# breakout.net
KiCad netlist of a schematic drawn in EAGLE
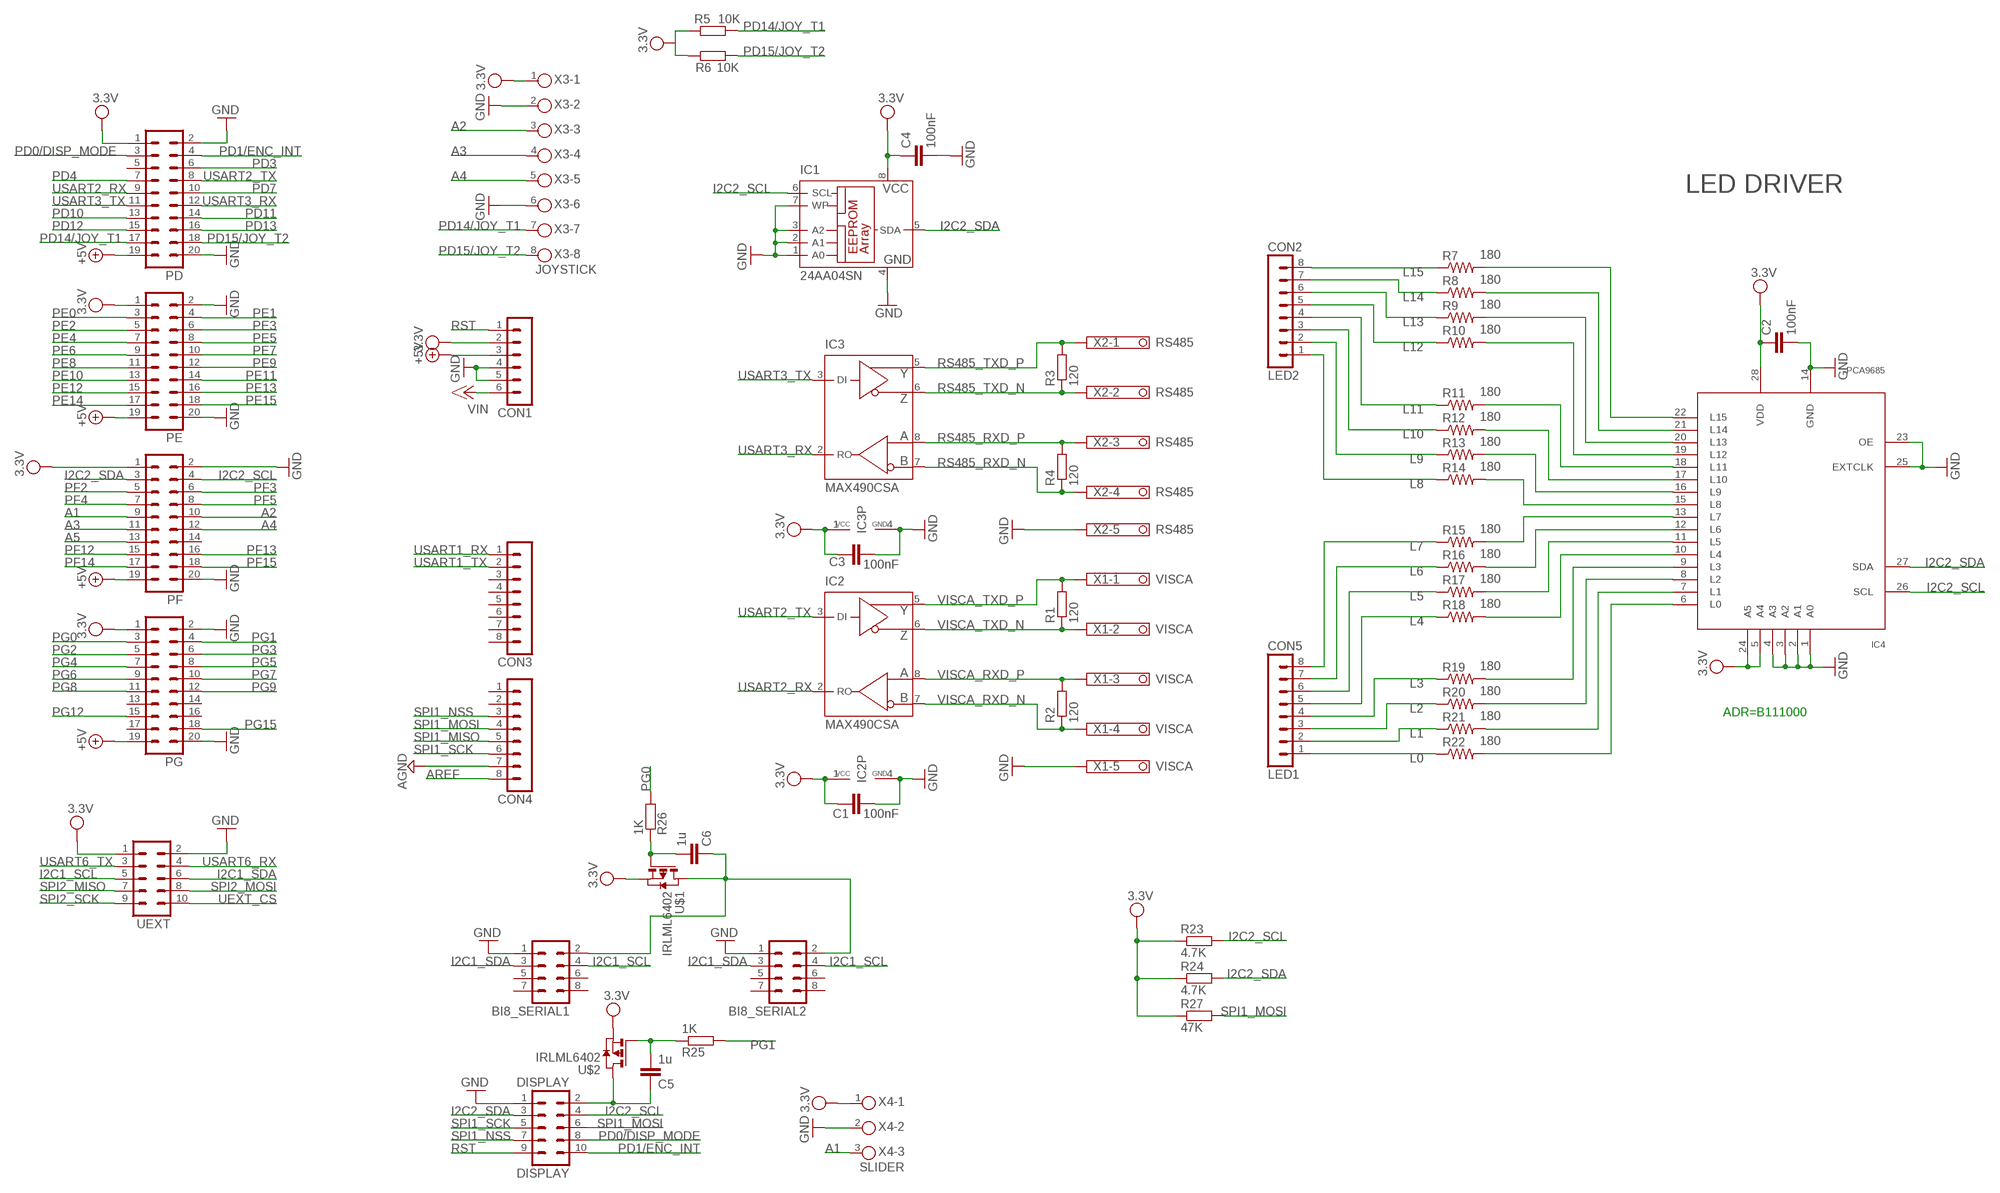
[diagram p0: schematic, sheet 1]

(export (version "E")
  (design (tool "Eeschema 10.0.6"))
  (components
    (comp (ref "BI8_SERIAL1")
      (value "MA04-2")
      (footprint "eagle-import:MA04-2")
      (libsource (lib "eagle-import") (part "MA04-2"))
    )
    (comp (ref "BI8_SERIAL2")
      (value "MA04-2")
      (footprint "eagle-import:MA04-2")
      (libsource (lib "eagle-import") (part "MA04-2"))
    )
    (comp (ref "C1")
      (value "100nF")
      (footprint "eagle-import:0603-CAP")
      (libsource (lib "eagle-import") (part "CAP0603-CAP"))
    )
    (comp (ref "C2")
      (value "100nF")
      (footprint "eagle-import:0603-CAP")
      (libsource (lib "eagle-import") (part "CAP0603-CAP"))
    )
    (comp (ref "C3")
      (value "100nF")
      (footprint "eagle-import:0603-CAP")
      (libsource (lib "eagle-import") (part "CAP0603-CAP"))
    )
    (comp (ref "C4")
      (value "100nF")
      (footprint "eagle-import:0603-CAP")
      (libsource (lib "eagle-import") (part "CAP0603-CAP"))
    )
    (comp (ref "C5")
      (value "1u")
      (footprint "eagle-import:C0805")
      (libsource (lib "eagle-import") (part "C-EUC0805"))
    )
    (comp (ref "C6")
      (value "1u")
      (footprint "eagle-import:C0805")
      (libsource (lib "eagle-import") (part "C-EUC0805"))
    )
    (comp (ref "CON1")
      (value "MA06-1")
      (footprint "eagle-import:MA06-1")
      (libsource (lib "eagle-import") (part "MA06-1"))
    )
    (comp (ref "CON2")
      (value "LED2")
      (footprint "eagle-import:MA08-1")
      (libsource (lib "eagle-import") (part "MA08-1"))
    )
    (comp (ref "CON3")
      (value "MA08-1")
      (footprint "eagle-import:MA08-1")
      (libsource (lib "eagle-import") (part "MA08-1"))
    )
    (comp (ref "CON4")
      (value "MA08-1")
      (footprint "eagle-import:MA08-1")
      (libsource (lib "eagle-import") (part "MA08-1"))
    )
    (comp (ref "CON5")
      (value "LED1")
      (footprint "eagle-import:MA08-1")
      (libsource (lib "eagle-import") (part "MA08-1"))
    )
    (comp (ref "DISPLAY")
      (value "DISPLAY")
      (footprint "eagle-import:MA05-2")
      (libsource (lib "eagle-import") (part "MA05-2"))
    )
    (comp (ref "IC1")
      (value "24AA04SN")
      (footprint "eagle-import:SO-08")
      (fields (field (name "MF") "MICROCHIP") (field (name "MPN") "24AA04/SN"))
      (libsource (lib "eagle-import") (part "24SNAA04"))
    )
    (comp (ref "IC2")
      (value "MAX490CSA")
      (footprint "eagle-import:SO08")
      (fields (field (name "MF") "MAXIM") (field (name "MPN") "MAX488CSA"))
      (libsource (lib "eagle-import") (part "MAX488CSA"))
    )
    (comp (ref "IC3")
      (value "MAX490CSA")
      (footprint "eagle-import:SO08")
      (fields (field (name "MF") "MAXIM") (field (name "MPN") "MAX488CSA"))
      (libsource (lib "eagle-import") (part "MAX488CSA"))
    )
    (comp (ref "IC4")
      (value "PCA9685")
      (footprint "eagle-import:TSSOP28")
      (libsource (lib "eagle-import") (part "PCA9685"))
    )
    (comp (ref "PD")
      (value "MA10-2")
      (footprint "eagle-import:MA10-2")
      (libsource (lib "eagle-import") (part "MA10-2"))
    )
    (comp (ref "PE")
      (value "MA10-2")
      (footprint "eagle-import:MA10-2")
      (libsource (lib "eagle-import") (part "MA10-2"))
    )
    (comp (ref "PF")
      (value "MA10-2")
      (footprint "eagle-import:MA10-2")
      (libsource (lib "eagle-import") (part "MA10-2"))
    )
    (comp (ref "PG")
      (value "MA10-2")
      (footprint "eagle-import:MA10-2")
      (libsource (lib "eagle-import") (part "MA10-2"))
    )
    (comp (ref "R1")
      (value "120")
      (footprint "eagle-import:R0603")
      (libsource (lib "eagle-import") (part "R-EU_R0603"))
    )
    (comp (ref "R2")
      (value "120")
      (footprint "eagle-import:R0603")
      (libsource (lib "eagle-import") (part "R-EU_R0603"))
    )
    (comp (ref "R3")
      (value "120")
      (footprint "eagle-import:R0603")
      (libsource (lib "eagle-import") (part "R-EU_R0603"))
    )
    (comp (ref "R4")
      (value "120")
      (footprint "eagle-import:R0603")
      (libsource (lib "eagle-import") (part "R-EU_R0603"))
    )
    (comp (ref "R5")
      (value "10K")
      (footprint "eagle-import:R0603")
      (libsource (lib "eagle-import") (part "R-EU_R0603"))
    )
    (comp (ref "R6")
      (value "10K")
      (footprint "eagle-import:R0603")
      (libsource (lib "eagle-import") (part "R-EU_R0603"))
    )
    (comp (ref "R7")
      (value "180")
      (footprint "eagle-import:0603-RES")
      (libsource (lib "eagle-import") (part "RESISTOR0603-RES"))
    )
    (comp (ref "R8")
      (value "180")
      (footprint "eagle-import:0603-RES")
      (libsource (lib "eagle-import") (part "RESISTOR0603-RES"))
    )
    (comp (ref "R9")
      (value "180")
      (footprint "eagle-import:0603-RES")
      (libsource (lib "eagle-import") (part "RESISTOR0603-RES"))
    )
    (comp (ref "R10")
      (value "180")
      (footprint "eagle-import:0603-RES")
      (libsource (lib "eagle-import") (part "RESISTOR0603-RES"))
    )
    (comp (ref "R11")
      (value "180")
      (footprint "eagle-import:0603-RES")
      (libsource (lib "eagle-import") (part "RESISTOR0603-RES"))
    )
    (comp (ref "R12")
      (value "180")
      (footprint "eagle-import:0603-RES")
      (libsource (lib "eagle-import") (part "RESISTOR0603-RES"))
    )
    (comp (ref "R13")
      (value "180")
      (footprint "eagle-import:0603-RES")
      (libsource (lib "eagle-import") (part "RESISTOR0603-RES"))
    )
    (comp (ref "R14")
      (value "180")
      (footprint "eagle-import:0603-RES")
      (libsource (lib "eagle-import") (part "RESISTOR0603-RES"))
    )
    (comp (ref "R15")
      (value "180")
      (footprint "eagle-import:0603-RES")
      (libsource (lib "eagle-import") (part "RESISTOR0603-RES"))
    )
    (comp (ref "R16")
      (value "180")
      (footprint "eagle-import:0603-RES")
      (libsource (lib "eagle-import") (part "RESISTOR0603-RES"))
    )
    (comp (ref "R17")
      (value "180")
      (footprint "eagle-import:0603-RES")
      (libsource (lib "eagle-import") (part "RESISTOR0603-RES"))
    )
    (comp (ref "R18")
      (value "180")
      (footprint "eagle-import:0603-RES")
      (libsource (lib "eagle-import") (part "RESISTOR0603-RES"))
    )
    (comp (ref "R19")
      (value "180")
      (footprint "eagle-import:0603-RES")
      (libsource (lib "eagle-import") (part "RESISTOR0603-RES"))
    )
    (comp (ref "R20")
      (value "180")
      (footprint "eagle-import:0603-RES")
      (libsource (lib "eagle-import") (part "RESISTOR0603-RES"))
    )
    (comp (ref "R21")
      (value "180")
      (footprint "eagle-import:0603-RES")
      (libsource (lib "eagle-import") (part "RESISTOR0603-RES"))
    )
    (comp (ref "R22")
      (value "180")
      (footprint "eagle-import:0603-RES")
      (libsource (lib "eagle-import") (part "RESISTOR0603-RES"))
    )
    (comp (ref "R23")
      (value "4.7K")
      (footprint "eagle-import:R0603")
      (libsource (lib "eagle-import") (part "R-EU_R0603"))
    )
    (comp (ref "R24")
      (value "4.7K")
      (footprint "eagle-import:R0603")
      (libsource (lib "eagle-import") (part "R-EU_R0603"))
    )
    (comp (ref "R25")
      (value "1K")
      (footprint "eagle-import:R0603")
      (libsource (lib "eagle-import") (part "R-EU_R0603"))
    )
    (comp (ref "R26")
      (value "1K")
      (footprint "eagle-import:R0603")
      (libsource (lib "eagle-import") (part "R-EU_R0603"))
    )
    (comp (ref "R27")
      (value "47K")
      (footprint "eagle-import:R0603")
      (libsource (lib "eagle-import") (part "R-EU_R0603"))
    )
    (comp (ref "U$1")
      (value "IRLML6402")
      (footprint "eagle-import:SOT-23")
      (libsource (lib "eagle-import") (part "IRLML6402"))
    )
    (comp (ref "U$2")
      (value "IRLML6402")
      (footprint "eagle-import:SOT-23")
      (libsource (lib "eagle-import") (part "IRLML6402"))
    )
    (comp (ref "UEXT")
      (value "ML10L")
      (footprint "eagle-import:ML10L")
      (libsource (lib "eagle-import") (part "ML10L"))
    )
    (comp (ref "X1")
      (value "VISCA")
      (footprint "eagle-import:1751277")
      (libsource (lib "eagle-import") (part "1751277"))
    )
    (comp (ref "X2")
      (value "RS485")
      (footprint "eagle-import:1751277")
      (libsource (lib "eagle-import") (part "1751277"))
    )
    (comp (ref "X3")
      (value "JOYSTICK")
      (footprint "eagle-import:8POL35")
      (libsource (lib "eagle-import") (part "AKL59-08"))
    )
    (comp (ref "X4")
      (value "SLIDER")
      (footprint "eagle-import:3POL35")
      (libsource (lib "eagle-import") (part "AKL59-03"))
    )
  )
  (nets
    (net (code "1") (name "+5V") (class "Default")
      (node (ref "CON1") (pin "3") (pinfunction "3_3") (pintype "passive"))
      (node (ref "PD") (pin "19") (pinfunction "19_19") (pintype "passive"))
      (node (ref "PE") (pin "19") (pinfunction "19_19") (pintype "passive"))
      (node (ref "PF") (pin "19") (pinfunction "19_19") (pintype "passive"))
      (node (ref "PG") (pin "19") (pinfunction "19_19") (pintype "passive"))
    )
    (net (code "2") (name "/A1") (class "Default")
      (node (ref "PF") (pin "9") (pinfunction "9_9") (pintype "passive"))
      (node (ref "X4") (pin "3") (pinfunction "1_3") (pintype "passive"))
    )
    (net (code "3") (name "/A2") (class "Default")
      (node (ref "PF") (pin "10") (pinfunction "10_10") (pintype "passive"))
      (node (ref "X3") (pin "3") (pinfunction "1_3") (pintype "passive"))
    )
    (net (code "4") (name "/A3") (class "Default")
      (node (ref "PF") (pin "11") (pinfunction "11_11") (pintype "passive"))
      (node (ref "X3") (pin "4") (pinfunction "1_4") (pintype "passive"))
    )
    (net (code "5") (name "/A4") (class "Default")
      (node (ref "PF") (pin "12") (pinfunction "12_12") (pintype "passive"))
      (node (ref "X3") (pin "5") (pinfunction "1_5") (pintype "passive"))
    )
    (net (code "6") (name "/A5") (class "Default")
      (node (ref "PF") (pin "13") (pinfunction "13_13") (pintype "passive"))
    )
    (net (code "7") (name "/AREF") (class "Default")
      (node (ref "CON4") (pin "8") (pinfunction "8_8") (pintype "passive"))
    )
    (net (code "8") (name "/I2C1_SCL") (class "Default")
      (node (ref "BI8_SERIAL1") (pin "4") (pinfunction "4_4") (pintype "passive"))
      (node (ref "BI8_SERIAL2") (pin "4") (pinfunction "4_4") (pintype "passive"))
      (node (ref "UEXT") (pin "5") (pinfunction "5_5") (pintype "passive"))
    )
    (net (code "9") (name "/I2C1_SDA") (class "Default")
      (node (ref "BI8_SERIAL1") (pin "3") (pinfunction "3_3") (pintype "passive"))
      (node (ref "BI8_SERIAL2") (pin "3") (pinfunction "3_3") (pintype "passive"))
      (node (ref "UEXT") (pin "6") (pinfunction "6_6") (pintype "passive"))
    )
    (net (code "10") (name "/I2C2_SCL") (class "Default")
      (node (ref "DISPLAY") (pin "4") (pinfunction "4_4") (pintype "passive"))
      (node (ref "IC1") (pin "6") (pinfunction "SCL_6") (pintype "input"))
      (node (ref "IC4") (pin "26") (pinfunction "SCL_26") (pintype "input"))
      (node (ref "PF") (pin "4") (pinfunction "4_4") (pintype "passive"))
      (node (ref "R23") (pin "2") (pinfunction "2_2") (pintype "passive"))
    )
    (net (code "11") (name "/I2C2_SDA") (class "Default")
      (node (ref "DISPLAY") (pin "3") (pinfunction "3_3") (pintype "passive"))
      (node (ref "IC1") (pin "5") (pinfunction "SDA_5") (pintype "bidirectional"))
      (node (ref "IC4") (pin "27") (pinfunction "SDA_27") (pintype "input"))
      (node (ref "PF") (pin "3") (pinfunction "3_3") (pintype "passive"))
      (node (ref "R24") (pin "2") (pinfunction "2_2") (pintype "passive"))
    )
    (net (code "12") (name "/L0") (class "Default")
      (node (ref "CON5") (pin "1") (pinfunction "1_1") (pintype "passive"))
      (node (ref "R22") (pin "1") (pinfunction "1_1") (pintype "passive"))
    )
    (net (code "13") (name "/L1") (class "Default")
      (node (ref "CON5") (pin "2") (pinfunction "2_2") (pintype "passive"))
      (node (ref "R21") (pin "1") (pinfunction "1_1") (pintype "passive"))
    )
    (net (code "14") (name "/L2") (class "Default")
      (node (ref "CON5") (pin "3") (pinfunction "3_3") (pintype "passive"))
      (node (ref "R20") (pin "1") (pinfunction "1_1") (pintype "passive"))
    )
    (net (code "15") (name "/L3") (class "Default")
      (node (ref "CON5") (pin "4") (pinfunction "4_4") (pintype "passive"))
      (node (ref "R19") (pin "1") (pinfunction "1_1") (pintype "passive"))
    )
    (net (code "16") (name "/L4") (class "Default")
      (node (ref "CON5") (pin "5") (pinfunction "5_5") (pintype "passive"))
      (node (ref "R18") (pin "1") (pinfunction "1_1") (pintype "passive"))
    )
    (net (code "17") (name "/L5") (class "Default")
      (node (ref "CON5") (pin "6") (pinfunction "6_6") (pintype "passive"))
      (node (ref "R17") (pin "1") (pinfunction "1_1") (pintype "passive"))
    )
    (net (code "18") (name "/L6") (class "Default")
      (node (ref "CON5") (pin "7") (pinfunction "7_7") (pintype "passive"))
      (node (ref "R16") (pin "1") (pinfunction "1_1") (pintype "passive"))
    )
    (net (code "19") (name "/L7") (class "Default")
      (node (ref "CON5") (pin "8") (pinfunction "8_8") (pintype "passive"))
      (node (ref "R15") (pin "1") (pinfunction "1_1") (pintype "passive"))
    )
    (net (code "20") (name "/L8") (class "Default")
      (node (ref "CON2") (pin "1") (pinfunction "1_1") (pintype "passive"))
      (node (ref "R14") (pin "1") (pinfunction "1_1") (pintype "passive"))
    )
    (net (code "21") (name "/L9") (class "Default")
      (node (ref "CON2") (pin "2") (pinfunction "2_2") (pintype "passive"))
      (node (ref "R13") (pin "1") (pinfunction "1_1") (pintype "passive"))
    )
    (net (code "22") (name "/L10") (class "Default")
      (node (ref "CON2") (pin "3") (pinfunction "3_3") (pintype "passive"))
      (node (ref "R12") (pin "1") (pinfunction "1_1") (pintype "passive"))
    )
    (net (code "23") (name "/L11") (class "Default")
      (node (ref "CON2") (pin "4") (pinfunction "4_4") (pintype "passive"))
      (node (ref "R11") (pin "1") (pinfunction "1_1") (pintype "passive"))
    )
    (net (code "24") (name "/L12") (class "Default")
      (node (ref "CON2") (pin "5") (pinfunction "5_5") (pintype "passive"))
      (node (ref "R10") (pin "1") (pinfunction "1_1") (pintype "passive"))
    )
    (net (code "25") (name "/L13") (class "Default")
      (node (ref "CON2") (pin "6") (pinfunction "6_6") (pintype "passive"))
      (node (ref "R9") (pin "1") (pinfunction "1_1") (pintype "passive"))
    )
    (net (code "26") (name "/L14") (class "Default")
      (node (ref "CON2") (pin "7") (pinfunction "7_7") (pintype "passive"))
      (node (ref "R8") (pin "1") (pinfunction "1_1") (pintype "passive"))
    )
    (net (code "27") (name "/L15") (class "Default")
      (node (ref "CON2") (pin "8") (pinfunction "8_8") (pintype "passive"))
      (node (ref "R7") (pin "1") (pinfunction "1_1") (pintype "passive"))
    )
    (net (code "28") (name "/PD0{slash}DISP_MODE") (class "Default")
      (node (ref "DISPLAY") (pin "8") (pinfunction "8_8") (pintype "passive"))
      (node (ref "PD") (pin "3") (pinfunction "3_3") (pintype "passive"))
    )
    (net (code "29") (name "/PD1{slash}ENC_INT") (class "Default")
      (node (ref "DISPLAY") (pin "10") (pinfunction "10_10") (pintype "passive"))
      (node (ref "PD") (pin "4") (pinfunction "4_4") (pintype "passive"))
    )
    (net (code "30") (name "/PD3") (class "Default")
      (node (ref "PD") (pin "6") (pinfunction "6_6") (pintype "passive"))
    )
    (net (code "31") (name "/PD4") (class "Default")
      (node (ref "PD") (pin "7") (pinfunction "7_7") (pintype "passive"))
    )
    (net (code "32") (name "/PD7") (class "Default")
      (node (ref "PD") (pin "10") (pinfunction "10_10") (pintype "passive"))
    )
    (net (code "33") (name "/PD10") (class "Default")
      (node (ref "PD") (pin "13") (pinfunction "13_13") (pintype "passive"))
    )
    (net (code "34") (name "/PD11") (class "Default")
      (node (ref "PD") (pin "14") (pinfunction "14_14") (pintype "passive"))
    )
    (net (code "35") (name "/PD12") (class "Default")
      (node (ref "PD") (pin "15") (pinfunction "15_15") (pintype "passive"))
    )
    (net (code "36") (name "/PD13") (class "Default")
      (node (ref "PD") (pin "16") (pinfunction "16_16") (pintype "passive"))
    )
    (net (code "37") (name "/PD14{slash}JOY_T1") (class "Default")
      (node (ref "PD") (pin "17") (pinfunction "17_17") (pintype "passive"))
      (node (ref "R5") (pin "2") (pinfunction "2_2") (pintype "passive"))
      (node (ref "X3") (pin "7") (pinfunction "1_7") (pintype "passive"))
    )
    (net (code "38") (name "/PD15{slash}JOY_T2") (class "Default")
      (node (ref "PD") (pin "18") (pinfunction "18_18") (pintype "passive"))
      (node (ref "R6") (pin "2") (pinfunction "2_2") (pintype "passive"))
      (node (ref "X3") (pin "8") (pinfunction "1_8") (pintype "passive"))
    )
    (net (code "39") (name "/PE0") (class "Default")
      (node (ref "PE") (pin "3") (pinfunction "3_3") (pintype "passive"))
    )
    (net (code "40") (name "/PE1") (class "Default")
      (node (ref "PE") (pin "4") (pinfunction "4_4") (pintype "passive"))
    )
    (net (code "41") (name "/PE2") (class "Default")
      (node (ref "PE") (pin "5") (pinfunction "5_5") (pintype "passive"))
    )
    (net (code "42") (name "/PE3") (class "Default")
      (node (ref "PE") (pin "6") (pinfunction "6_6") (pintype "passive"))
    )
    (net (code "43") (name "/PE4") (class "Default")
      (node (ref "PE") (pin "7") (pinfunction "7_7") (pintype "passive"))
    )
    (net (code "44") (name "/PE5") (class "Default")
      (node (ref "PE") (pin "8") (pinfunction "8_8") (pintype "passive"))
    )
    (net (code "45") (name "/PE6") (class "Default")
      (node (ref "PE") (pin "9") (pinfunction "9_9") (pintype "passive"))
    )
    (net (code "46") (name "/PE7") (class "Default")
      (node (ref "PE") (pin "10") (pinfunction "10_10") (pintype "passive"))
    )
    (net (code "47") (name "/PE8") (class "Default")
      (node (ref "PE") (pin "11") (pinfunction "11_11") (pintype "passive"))
    )
    (net (code "48") (name "/PE9") (class "Default")
      (node (ref "PE") (pin "12") (pinfunction "12_12") (pintype "passive"))
    )
    (net (code "49") (name "/PE10") (class "Default")
      (node (ref "PE") (pin "13") (pinfunction "13_13") (pintype "passive"))
    )
    (net (code "50") (name "/PE11") (class "Default")
      (node (ref "PE") (pin "14") (pinfunction "14_14") (pintype "passive"))
    )
    (net (code "51") (name "/PE12") (class "Default")
      (node (ref "PE") (pin "15") (pinfunction "15_15") (pintype "passive"))
    )
    (net (code "52") (name "/PE13") (class "Default")
      (node (ref "PE") (pin "16") (pinfunction "16_16") (pintype "passive"))
    )
    (net (code "53") (name "/PE14") (class "Default")
      (node (ref "PE") (pin "17") (pinfunction "17_17") (pintype "passive"))
    )
    (net (code "54") (name "/PE15") (class "Default")
      (node (ref "PE") (pin "18") (pinfunction "18_18") (pintype "passive"))
    )
    (net (code "55") (name "/PF2") (class "Default")
      (node (ref "PF") (pin "5") (pinfunction "5_5") (pintype "passive"))
    )
    (net (code "56") (name "/PF3") (class "Default")
      (node (ref "PF") (pin "6") (pinfunction "6_6") (pintype "passive"))
    )
    (net (code "57") (name "/PF4") (class "Default")
      (node (ref "PF") (pin "7") (pinfunction "7_7") (pintype "passive"))
    )
    (net (code "58") (name "/PF5") (class "Default")
      (node (ref "PF") (pin "8") (pinfunction "8_8") (pintype "passive"))
    )
    (net (code "59") (name "/PF12") (class "Default")
      (node (ref "PF") (pin "15") (pinfunction "15_15") (pintype "passive"))
    )
    (net (code "60") (name "/PF13") (class "Default")
      (node (ref "PF") (pin "16") (pinfunction "16_16") (pintype "passive"))
    )
    (net (code "61") (name "/PF14") (class "Default")
      (node (ref "PF") (pin "17") (pinfunction "17_17") (pintype "passive"))
    )
    (net (code "62") (name "/PF15") (class "Default")
      (node (ref "PF") (pin "18") (pinfunction "18_18") (pintype "passive"))
    )
    (net (code "63") (name "/PG0") (class "Default")
      (node (ref "PG") (pin "3") (pinfunction "3_3") (pintype "passive"))
      (node (ref "R26") (pin "2") (pinfunction "2_2") (pintype "passive"))
    )
    (net (code "64") (name "/PG1") (class "Default")
      (node (ref "PG") (pin "4") (pinfunction "4_4") (pintype "passive"))
      (node (ref "R25") (pin "2") (pinfunction "2_2") (pintype "passive"))
    )
    (net (code "65") (name "/PG2") (class "Default")
      (node (ref "PG") (pin "5") (pinfunction "5_5") (pintype "passive"))
    )
    (net (code "66") (name "/PG3") (class "Default")
      (node (ref "PG") (pin "6") (pinfunction "6_6") (pintype "passive"))
    )
    (net (code "67") (name "/PG4") (class "Default")
      (node (ref "PG") (pin "7") (pinfunction "7_7") (pintype "passive"))
    )
    (net (code "68") (name "/PG5") (class "Default")
      (node (ref "PG") (pin "8") (pinfunction "8_8") (pintype "passive"))
    )
    (net (code "69") (name "/PG6") (class "Default")
      (node (ref "PG") (pin "9") (pinfunction "9_9") (pintype "passive"))
    )
    (net (code "70") (name "/PG7") (class "Default")
      (node (ref "PG") (pin "10") (pinfunction "10_10") (pintype "passive"))
    )
    (net (code "71") (name "/PG8") (class "Default")
      (node (ref "PG") (pin "11") (pinfunction "11_11") (pintype "passive"))
    )
    (net (code "72") (name "/PG9") (class "Default")
      (node (ref "PG") (pin "12") (pinfunction "12_12") (pintype "passive"))
    )
    (net (code "73") (name "/PG12") (class "Default")
      (node (ref "PG") (pin "15") (pinfunction "15_15") (pintype "passive"))
    )
    (net (code "74") (name "/PG15") (class "Default")
      (node (ref "PG") (pin "18") (pinfunction "18_18") (pintype "passive"))
    )
    (net (code "75") (name "/RS485_RXD_N") (class "Default")
      (node (ref "IC3") (pin "7") (pinfunction "B_7") (pintype "input"))
      (node (ref "R4") (pin "1") (pinfunction "1_1") (pintype "passive"))
      (node (ref "X2") (pin "4") (pinfunction "K_4") (pintype "passive"))
    )
    (net (code "76") (name "/RS485_RXD_P") (class "Default")
      (node (ref "IC3") (pin "8") (pinfunction "A_8") (pintype "input"))
      (node (ref "R4") (pin "2") (pinfunction "2_2") (pintype "passive"))
      (node (ref "X2") (pin "3") (pinfunction "K_3") (pintype "passive"))
    )
    (net (code "77") (name "/RS485_TXD_N") (class "Default")
      (node (ref "IC3") (pin "6") (pinfunction "Z_6") (pintype "output"))
      (node (ref "R3") (pin "1") (pinfunction "1_1") (pintype "passive"))
      (node (ref "X2") (pin "2") (pinfunction "K_2") (pintype "passive"))
    )
    (net (code "78") (name "/RS485_TXD_P") (class "Default")
      (node (ref "IC3") (pin "5") (pinfunction "Y_5") (pintype "output"))
      (node (ref "R3") (pin "2") (pinfunction "2_2") (pintype "passive"))
      (node (ref "X2") (pin "1") (pinfunction "K_1") (pintype "passive"))
    )
    (net (code "79") (name "/RST") (class "Default")
      (node (ref "CON1") (pin "1") (pinfunction "1_1") (pintype "passive"))
      (node (ref "DISPLAY") (pin "9") (pinfunction "9_9") (pintype "passive"))
    )
    (net (code "80") (name "/SPI1_MISO") (class "Default")
      (node (ref "CON4") (pin "5") (pinfunction "5_5") (pintype "passive"))
    )
    (net (code "81") (name "/SPI1_MOSI") (class "Default")
      (node (ref "CON4") (pin "4") (pinfunction "4_4") (pintype "passive"))
      (node (ref "DISPLAY") (pin "6") (pinfunction "6_6") (pintype "passive"))
      (node (ref "R27") (pin "2") (pinfunction "2_2") (pintype "passive"))
    )
    (net (code "82") (name "/SPI1_NSS") (class "Default")
      (node (ref "CON4") (pin "3") (pinfunction "3_3") (pintype "passive"))
      (node (ref "DISPLAY") (pin "7") (pinfunction "7_7") (pintype "passive"))
    )
    (net (code "83") (name "/SPI1_SCK") (class "Default")
      (node (ref "CON4") (pin "6") (pinfunction "6_6") (pintype "passive"))
      (node (ref "DISPLAY") (pin "5") (pinfunction "5_5") (pintype "passive"))
    )
    (net (code "84") (name "/SPI2_MISO") (class "Default")
      (node (ref "UEXT") (pin "7") (pinfunction "7_7") (pintype "passive"))
    )
    (net (code "85") (name "/SPI2_MOSI") (class "Default")
      (node (ref "UEXT") (pin "8") (pinfunction "8_8") (pintype "passive"))
    )
    (net (code "86") (name "/SPI2_SCK") (class "Default")
      (node (ref "UEXT") (pin "9") (pinfunction "9_9") (pintype "passive"))
    )
    (net (code "87") (name "/UEXT_CS") (class "Default")
      (node (ref "UEXT") (pin "10") (pinfunction "10_10") (pintype "passive"))
    )
    (net (code "88") (name "/USART1_RX") (class "Default")
      (node (ref "CON3") (pin "1") (pinfunction "1_1") (pintype "passive"))
    )
    (net (code "89") (name "/USART1_TX") (class "Default")
      (node (ref "CON3") (pin "2") (pinfunction "2_2") (pintype "passive"))
    )
    (net (code "90") (name "/USART2_RX") (class "Default")
      (node (ref "IC2") (pin "2") (pinfunction "RO_2") (pintype "output"))
      (node (ref "PD") (pin "9") (pinfunction "9_9") (pintype "passive"))
    )
    (net (code "91") (name "/USART2_TX") (class "Default")
      (node (ref "IC2") (pin "3") (pinfunction "DI_3") (pintype "input"))
      (node (ref "PD") (pin "8") (pinfunction "8_8") (pintype "passive"))
    )
    (net (code "92") (name "/USART3_RX") (class "Default")
      (node (ref "IC3") (pin "2") (pinfunction "RO_2") (pintype "output"))
      (node (ref "PD") (pin "12") (pinfunction "12_12") (pintype "passive"))
    )
    (net (code "93") (name "/USART3_TX") (class "Default")
      (node (ref "IC3") (pin "3") (pinfunction "DI_3") (pintype "input"))
      (node (ref "PD") (pin "11") (pinfunction "11_11") (pintype "passive"))
    )
    (net (code "94") (name "/USART6_RX") (class "Default")
      (node (ref "UEXT") (pin "4") (pinfunction "4_4") (pintype "passive"))
    )
    (net (code "95") (name "/USART6_TX") (class "Default")
      (node (ref "UEXT") (pin "3") (pinfunction "3_3") (pintype "passive"))
    )
    (net (code "96") (name "/VISCA_RXD_N") (class "Default")
      (node (ref "IC2") (pin "7") (pinfunction "B_7") (pintype "input"))
      (node (ref "R2") (pin "1") (pinfunction "1_1") (pintype "passive"))
      (node (ref "X1") (pin "4") (pinfunction "K_4") (pintype "passive"))
    )
    (net (code "97") (name "/VISCA_RXD_P") (class "Default")
      (node (ref "IC2") (pin "8") (pinfunction "A_8") (pintype "input"))
      (node (ref "R2") (pin "2") (pinfunction "2_2") (pintype "passive"))
      (node (ref "X1") (pin "3") (pinfunction "K_3") (pintype "passive"))
    )
    (net (code "98") (name "/VISCA_TXD_N") (class "Default")
      (node (ref "IC2") (pin "6") (pinfunction "Z_6") (pintype "output"))
      (node (ref "R1") (pin "1") (pinfunction "1_1") (pintype "passive"))
      (node (ref "X1") (pin "2") (pinfunction "K_2") (pintype "passive"))
    )
    (net (code "99") (name "/VISCA_TXD_P") (class "Default")
      (node (ref "IC2") (pin "5") (pinfunction "Y_5") (pintype "output"))
      (node (ref "R1") (pin "2") (pinfunction "2_2") (pintype "passive"))
      (node (ref "X1") (pin "1") (pinfunction "K_1") (pintype "passive"))
    )
    (net (code "100") (name "3.3V") (class "Default")
      (node (ref "C1") (pin "1") (pinfunction "1_1") (pintype "passive"))
      (node (ref "C2") (pin "1") (pinfunction "1_1") (pintype "passive"))
      (node (ref "C3") (pin "1") (pinfunction "1_1") (pintype "passive"))
      (node (ref "C4") (pin "1") (pinfunction "1_1") (pintype "passive"))
      (node (ref "CON1") (pin "2") (pinfunction "2_2") (pintype "passive"))
      (node (ref "IC1") (pin "8") (pinfunction "VCC_8") (pintype "power_in"))
      (node (ref "IC2") (pin "1") (pinfunction "VCC_1") (pintype "power_in"))
      (node (ref "IC3") (pin "1") (pinfunction "VCC_1") (pintype "power_in"))
      (node (ref "IC4") (pin "24") (pinfunction "A5_24") (pintype "input"))
      (node (ref "IC4") (pin "28") (pinfunction "VDD_28") (pintype "power_in"))
      (node (ref "IC4") (pin "5") (pinfunction "A4_5") (pintype "input"))
      (node (ref "PD") (pin "1") (pinfunction "1_1") (pintype "passive"))
      (node (ref "PE") (pin "1") (pinfunction "1_1") (pintype "passive"))
      (node (ref "PF") (pin "1") (pinfunction "1_1") (pintype "passive"))
      (node (ref "PG") (pin "1") (pinfunction "1_1") (pintype "passive"))
      (node (ref "R23") (pin "1") (pinfunction "1_1") (pintype "passive"))
      (node (ref "R24") (pin "1") (pinfunction "1_1") (pintype "passive"))
      (node (ref "R27") (pin "1") (pinfunction "1_1") (pintype "passive"))
      (node (ref "R5") (pin "1") (pinfunction "1_1") (pintype "passive"))
      (node (ref "R6") (pin "1") (pinfunction "1_1") (pintype "passive"))
      (node (ref "U$1") (pin "2") (pinfunction "S_2") (pintype "passive"))
      (node (ref "U$2") (pin "2") (pinfunction "S_2") (pintype "passive"))
      (node (ref "UEXT") (pin "1") (pinfunction "1_1") (pintype "passive"))
      (node (ref "X3") (pin "1") (pinfunction "1_1") (pintype "passive"))
      (node (ref "X4") (pin "1") (pinfunction "1_1") (pintype "passive"))
    )
    (net (code "101") (name "AGND") (class "Default")
      (node (ref "CON4") (pin "7") (pinfunction "7_7") (pintype "passive"))
    )
    (net (code "102") (name "GND") (class "Default")
      (node (ref "BI8_SERIAL1") (pin "1") (pinfunction "1_1") (pintype "passive"))
      (node (ref "BI8_SERIAL2") (pin "1") (pinfunction "1_1") (pintype "passive"))
      (node (ref "C1") (pin "2") (pinfunction "2_2") (pintype "passive"))
      (node (ref "C2") (pin "2") (pinfunction "2_2") (pintype "passive"))
      (node (ref "C3") (pin "2") (pinfunction "2_2") (pintype "passive"))
      (node (ref "C4") (pin "2") (pinfunction "2_2") (pintype "passive"))
      (node (ref "CON1") (pin "4") (pinfunction "4_4") (pintype "passive"))
      (node (ref "CON1") (pin "5") (pinfunction "5_5") (pintype "passive"))
      (node (ref "DISPLAY") (pin "1") (pinfunction "1_1") (pintype "passive"))
      (node (ref "IC1") (pin "1") (pinfunction "A0_1") (pintype "input"))
      (node (ref "IC1") (pin "2") (pinfunction "A1_2") (pintype "input"))
      (node (ref "IC1") (pin "3") (pinfunction "A2_3") (pintype "input"))
      (node (ref "IC1") (pin "4") (pinfunction "GND_4") (pintype "power_in"))
      (node (ref "IC1") (pin "7") (pinfunction "WP_7") (pintype "input"))
      (node (ref "IC2") (pin "4") (pinfunction "GND_4") (pintype "power_in"))
      (node (ref "IC3") (pin "4") (pinfunction "GND_4") (pintype "power_in"))
      (node (ref "IC4") (pin "1") (pinfunction "A0_1") (pintype "input"))
      (node (ref "IC4") (pin "14") (pinfunction "GND_14") (pintype "power_in"))
      (node (ref "IC4") (pin "2") (pinfunction "A1_2") (pintype "input"))
      (node (ref "IC4") (pin "23") (pinfunction "OE_23") (pintype "input"))
      (node (ref "IC4") (pin "25") (pinfunction "EXTCLK_25") (pintype "input"))
      (node (ref "IC4") (pin "3") (pinfunction "A2_3") (pintype "input"))
      (node (ref "IC4") (pin "4") (pinfunction "A3_4") (pintype "input"))
      (node (ref "PD") (pin "2") (pinfunction "2_2") (pintype "passive"))
      (node (ref "PD") (pin "20") (pinfunction "20_20") (pintype "passive"))
      (node (ref "PE") (pin "2") (pinfunction "2_2") (pintype "passive"))
      (node (ref "PE") (pin "20") (pinfunction "20_20") (pintype "passive"))
      (node (ref "PF") (pin "2") (pinfunction "2_2") (pintype "passive"))
      (node (ref "PF") (pin "20") (pinfunction "20_20") (pintype "passive"))
      (node (ref "PG") (pin "2") (pinfunction "2_2") (pintype "passive"))
      (node (ref "PG") (pin "20") (pinfunction "20_20") (pintype "passive"))
      (node (ref "UEXT") (pin "2") (pinfunction "2_2") (pintype "passive"))
      (node (ref "X1") (pin "5") (pinfunction "K_5") (pintype "passive"))
      (node (ref "X2") (pin "5") (pinfunction "K_5") (pintype "passive"))
      (node (ref "X3") (pin "2") (pinfunction "1_2") (pintype "passive"))
      (node (ref "X3") (pin "6") (pinfunction "1_6") (pintype "passive"))
      (node (ref "X4") (pin "2") (pinfunction "1_2") (pintype "passive"))
    )
    (net (code "103") (name "Net-(IC4-L0)") (class "Default")
      (node (ref "IC4") (pin "6") (pinfunction "L0_6") (pintype "output"))
      (node (ref "R22") (pin "2") (pinfunction "2_2") (pintype "passive"))
    )
    (net (code "104") (name "Net-(IC4-L1)") (class "Default")
      (node (ref "IC4") (pin "7") (pinfunction "L1_7") (pintype "output"))
      (node (ref "R21") (pin "2") (pinfunction "2_2") (pintype "passive"))
    )
    (net (code "105") (name "Net-(IC4-L2)") (class "Default")
      (node (ref "IC4") (pin "8") (pinfunction "L2_8") (pintype "output"))
      (node (ref "R20") (pin "2") (pinfunction "2_2") (pintype "passive"))
    )
    (net (code "106") (name "Net-(IC4-L3)") (class "Default")
      (node (ref "IC4") (pin "9") (pinfunction "L3_9") (pintype "output"))
      (node (ref "R19") (pin "2") (pinfunction "2_2") (pintype "passive"))
    )
    (net (code "107") (name "Net-(IC4-L4)") (class "Default")
      (node (ref "IC4") (pin "10") (pinfunction "L4_10") (pintype "output"))
      (node (ref "R18") (pin "2") (pinfunction "2_2") (pintype "passive"))
    )
    (net (code "108") (name "Net-(IC4-L5)") (class "Default")
      (node (ref "IC4") (pin "11") (pinfunction "L5_11") (pintype "output"))
      (node (ref "R17") (pin "2") (pinfunction "2_2") (pintype "passive"))
    )
    (net (code "109") (name "Net-(IC4-L6)") (class "Default")
      (node (ref "IC4") (pin "12") (pinfunction "L6_12") (pintype "output"))
      (node (ref "R16") (pin "2") (pinfunction "2_2") (pintype "passive"))
    )
    (net (code "110") (name "Net-(IC4-L7)") (class "Default")
      (node (ref "IC4") (pin "13") (pinfunction "L7_13") (pintype "output"))
      (node (ref "R15") (pin "2") (pinfunction "2_2") (pintype "passive"))
    )
    (net (code "111") (name "Net-(IC4-L8)") (class "Default")
      (node (ref "IC4") (pin "15") (pinfunction "L8_15") (pintype "output"))
      (node (ref "R14") (pin "2") (pinfunction "2_2") (pintype "passive"))
    )
    (net (code "112") (name "Net-(IC4-L9)") (class "Default")
      (node (ref "IC4") (pin "16") (pinfunction "L9_16") (pintype "output"))
      (node (ref "R13") (pin "2") (pinfunction "2_2") (pintype "passive"))
    )
    (net (code "113") (name "Net-(IC4-L10)") (class "Default")
      (node (ref "IC4") (pin "17") (pinfunction "L10_17") (pintype "output"))
      (node (ref "R12") (pin "2") (pinfunction "2_2") (pintype "passive"))
    )
    (net (code "114") (name "Net-(IC4-L11)") (class "Default")
      (node (ref "IC4") (pin "18") (pinfunction "L11_18") (pintype "output"))
      (node (ref "R11") (pin "2") (pinfunction "2_2") (pintype "passive"))
    )
    (net (code "115") (name "Net-(IC4-L12)") (class "Default")
      (node (ref "IC4") (pin "19") (pinfunction "L12_19") (pintype "output"))
      (node (ref "R10") (pin "2") (pinfunction "2_2") (pintype "passive"))
    )
    (net (code "116") (name "Net-(IC4-L13)") (class "Default")
      (node (ref "IC4") (pin "20") (pinfunction "L13_20") (pintype "output"))
      (node (ref "R9") (pin "2") (pinfunction "2_2") (pintype "passive"))
    )
    (net (code "117") (name "Net-(IC4-L14)") (class "Default")
      (node (ref "IC4") (pin "21") (pinfunction "L14_21") (pintype "output"))
      (node (ref "R8") (pin "2") (pinfunction "2_2") (pintype "passive"))
    )
    (net (code "118") (name "Net-(IC4-L15)") (class "Default")
      (node (ref "IC4") (pin "22") (pinfunction "L15_22") (pintype "output"))
      (node (ref "R7") (pin "2") (pinfunction "2_2") (pintype "passive"))
    )
    (net (code "119") (name "Net-(U$1-D)") (class "Default")
      (node (ref "BI8_SERIAL1") (pin "2") (pinfunction "2_2") (pintype "passive"))
      (node (ref "BI8_SERIAL2") (pin "2") (pinfunction "2_2") (pintype "passive"))
      (node (ref "C6") (pin "1") (pinfunction "1_1") (pintype "passive"))
      (node (ref "U$1") (pin "3") (pinfunction "D_3") (pintype "passive"))
    )
    (net (code "120") (name "Net-(U$1-G)") (class "Default")
      (node (ref "C6") (pin "2") (pinfunction "2_2") (pintype "passive"))
      (node (ref "R26") (pin "1") (pinfunction "1_1") (pintype "passive"))
      (node (ref "U$1") (pin "1") (pinfunction "G_1") (pintype "passive"))
    )
    (net (code "121") (name "Net-(U$2-D)") (class "Default")
      (node (ref "C5") (pin "1") (pinfunction "1_1") (pintype "passive"))
      (node (ref "DISPLAY") (pin "2") (pinfunction "2_2") (pintype "passive"))
      (node (ref "U$2") (pin "3") (pinfunction "D_3") (pintype "passive"))
    )
    (net (code "122") (name "Net-(U$2-G)") (class "Default")
      (node (ref "C5") (pin "2") (pinfunction "2_2") (pintype "passive"))
      (node (ref "R25") (pin "1") (pinfunction "1_1") (pintype "passive"))
      (node (ref "U$2") (pin "1") (pinfunction "G_1") (pintype "passive"))
    )
    (net (code "123") (name "VIN") (class "Default")
      (node (ref "CON1") (pin "6") (pinfunction "6_6") (pintype "passive"))
    )
    (net (code "124") (name "unconnected-(BI8_SERIAL1-Pad5)") (class "Default")
      (node (ref "BI8_SERIAL1") (pin "5") (pinfunction "5_5") (pintype "passive"))
    )
    (net (code "125") (name "unconnected-(BI8_SERIAL1-Pad6)") (class "Default")
      (node (ref "BI8_SERIAL1") (pin "6") (pinfunction "6_6") (pintype "passive"))
    )
    (net (code "126") (name "unconnected-(BI8_SERIAL1-Pad7)") (class "Default")
      (node (ref "BI8_SERIAL1") (pin "7") (pinfunction "7_7") (pintype "passive"))
    )
    (net (code "127") (name "unconnected-(BI8_SERIAL1-Pad8)") (class "Default")
      (node (ref "BI8_SERIAL1") (pin "8") (pinfunction "8_8") (pintype "passive"))
    )
    (net (code "128") (name "unconnected-(BI8_SERIAL2-Pad5)") (class "Default")
      (node (ref "BI8_SERIAL2") (pin "5") (pinfunction "5_5") (pintype "passive"))
    )
    (net (code "129") (name "unconnected-(BI8_SERIAL2-Pad6)") (class "Default")
      (node (ref "BI8_SERIAL2") (pin "6") (pinfunction "6_6") (pintype "passive"))
    )
    (net (code "130") (name "unconnected-(BI8_SERIAL2-Pad7)") (class "Default")
      (node (ref "BI8_SERIAL2") (pin "7") (pinfunction "7_7") (pintype "passive"))
    )
    (net (code "131") (name "unconnected-(BI8_SERIAL2-Pad8)") (class "Default")
      (node (ref "BI8_SERIAL2") (pin "8") (pinfunction "8_8") (pintype "passive"))
    )
    (net (code "132") (name "unconnected-(CON3-Pad3)") (class "Default")
      (node (ref "CON3") (pin "3") (pinfunction "3_3") (pintype "passive"))
    )
    (net (code "133") (name "unconnected-(CON3-Pad4)") (class "Default")
      (node (ref "CON3") (pin "4") (pinfunction "4_4") (pintype "passive"))
    )
    (net (code "134") (name "unconnected-(CON3-Pad5)") (class "Default")
      (node (ref "CON3") (pin "5") (pinfunction "5_5") (pintype "passive"))
    )
    (net (code "135") (name "unconnected-(CON3-Pad6)") (class "Default")
      (node (ref "CON3") (pin "6") (pinfunction "6_6") (pintype "passive"))
    )
    (net (code "136") (name "unconnected-(CON3-Pad7)") (class "Default")
      (node (ref "CON3") (pin "7") (pinfunction "7_7") (pintype "passive"))
    )
    (net (code "137") (name "unconnected-(CON3-Pad8)") (class "Default")
      (node (ref "CON3") (pin "8") (pinfunction "8_8") (pintype "passive"))
    )
    (net (code "138") (name "unconnected-(CON4-Pad1)") (class "Default")
      (node (ref "CON4") (pin "1") (pinfunction "1_1") (pintype "passive"))
    )
    (net (code "139") (name "unconnected-(CON4-Pad2)") (class "Default")
      (node (ref "CON4") (pin "2") (pinfunction "2_2") (pintype "passive"))
    )
    (net (code "140") (name "unconnected-(PD-Pad5)") (class "Default")
      (node (ref "PD") (pin "5") (pinfunction "5_5") (pintype "passive"))
    )
    (net (code "141") (name "unconnected-(PF-Pad14)") (class "Default")
      (node (ref "PF") (pin "14") (pinfunction "14_14") (pintype "passive"))
    )
    (net (code "142") (name "unconnected-(PG-Pad13)") (class "Default")
      (node (ref "PG") (pin "13") (pinfunction "13_13") (pintype "passive"))
    )
    (net (code "143") (name "unconnected-(PG-Pad14)") (class "Default")
      (node (ref "PG") (pin "14") (pinfunction "14_14") (pintype "passive"))
    )
    (net (code "144") (name "unconnected-(PG-Pad16)") (class "Default")
      (node (ref "PG") (pin "16") (pinfunction "16_16") (pintype "passive"))
    )
    (net (code "145") (name "unconnected-(PG-Pad17)") (class "Default")
      (node (ref "PG") (pin "17") (pinfunction "17_17") (pintype "passive"))
    )
  )
)
